# Boost-to-12V.net
KiCad netlist of a schematic drawn in Altium Designer
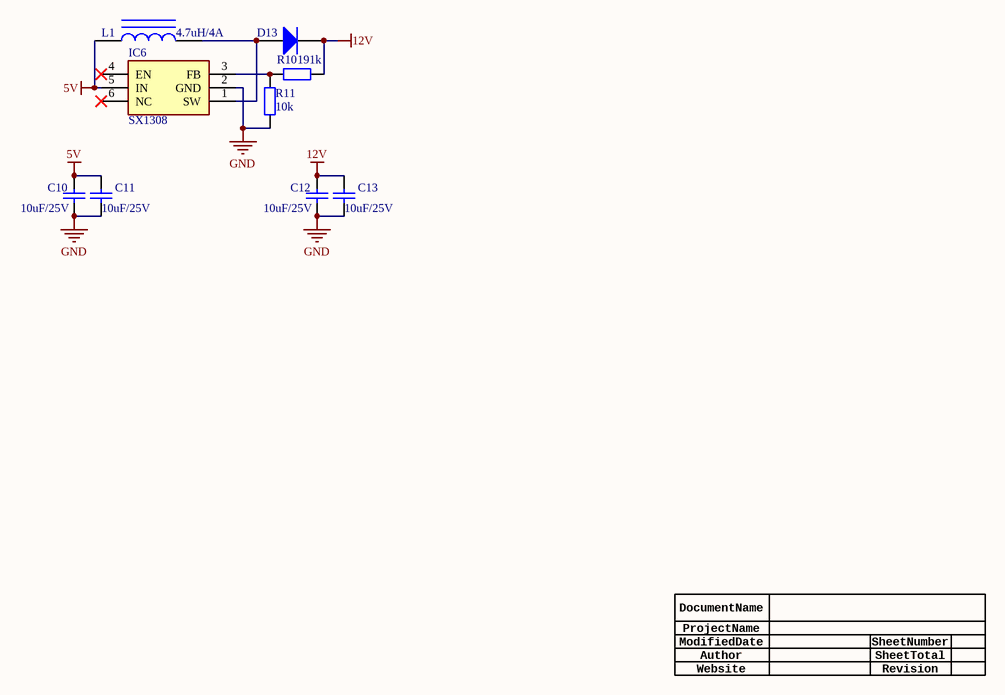
[diagram p0: Boost-to-12V.SchDoc]

(export (version "E")
  (design (tool "Eeschema 10.0.6"))
  (components
    (comp (ref "C10")
      (value "10uF/25V")
      (footprint "CAP-0603")
      (description "X7R")
      (libsource (lib "Power_Lib_Altium") (part "CAP"))
    )
    (comp (ref "C11")
      (value "10uF/25V")
      (footprint "CAP-0603")
      (description "X7R")
      (libsource (lib "Power_Lib_Altium") (part "CAP"))
    )
    (comp (ref "C12")
      (value "10uF/25V")
      (footprint "CAP-0603")
      (description "X7R")
      (libsource (lib "Power_Lib_Altium") (part "CAP"))
    )
    (comp (ref "C13")
      (value "10uF/25V")
      (footprint "CAP-0603")
      (description "X7R")
      (libsource (lib "Power_Lib_Altium") (part "CAP"))
    )
    (comp (ref "D13")
      (value "SS34")
      (footprint "DO-214AC/SMA")
      (description "二极管")
      (libsource (lib "Power_Lib_Altium") (part "DIODE"))
    )
    (comp (ref "IC6")
      (value "SX1308")
      (footprint "SOT-23-6")
      (description "集成升压芯片")
      (libsource (lib "Power_Lib_Altium") (part "SX1308"))
    )
    (comp (ref "L1")
      (value "4.7uH/4A")
      (footprint "SMD_7.3x7.3x4.2mm")
      (description "电感")
      (libsource (lib "Power_Lib_Altium") (part "INDUCTOR"))
    )
    (comp (ref "R10")
      (value "191k")
      (footprint "R-0603")
      (description "贴片电阻")
      (libsource (lib "Power_Lib_Altium") (part "RES"))
    )
    (comp (ref "R11")
      (value "10k")
      (footprint "R-0603")
      (description "贴片电阻")
      (libsource (lib "") (part "RES_1"))
    )
  )
  (nets
    (net (code "1") (name "5V") (class "Default")
      (node (ref "C10") (pin "2") (pinfunction "2_2") (pintype "passive"))
      (node (ref "C11") (pin "2") (pinfunction "2_2") (pintype "passive"))
      (node (ref "IC6") (pin "5") (pinfunction "IN_5") (pintype "passive"))
      (node (ref "L1") (pin "1") (pinfunction "1_1") (pintype "passive"))
    )
    (net (code "2") (name "12V") (class "Default")
      (node (ref "C12") (pin "2") (pinfunction "2_2") (pintype "passive"))
      (node (ref "C13") (pin "2") (pinfunction "2_2") (pintype "passive"))
      (node (ref "D13") (pin "2") (pinfunction "K_2") (pintype "passive"))
      (node (ref "R10") (pin "2") (pinfunction "2_2") (pintype "passive"))
    )
    (net (code "3") (name "GND") (class "Default")
      (node (ref "C10") (pin "1") (pinfunction "1_1") (pintype "passive"))
      (node (ref "C11") (pin "1") (pinfunction "1_1") (pintype "passive"))
      (node (ref "C12") (pin "1") (pinfunction "1_1") (pintype "passive"))
      (node (ref "C13") (pin "1") (pinfunction "1_1") (pintype "passive"))
      (node (ref "IC6") (pin "2") (pinfunction "GND_2") (pintype "passive"))
      (node (ref "R11") (pin "1") (pinfunction "1_1") (pintype "passive"))
    )
    (net (code "4") (name "Net-(D13-A)") (class "Default")
      (node (ref "D13") (pin "1") (pinfunction "A_1") (pintype "passive"))
      (node (ref "IC6") (pin "1") (pinfunction "SW_1") (pintype "passive"))
      (node (ref "L1") (pin "2") (pinfunction "2_2") (pintype "passive"))
    )
    (net (code "5") (name "Net-(IC6-FB)") (class "Default")
      (node (ref "IC6") (pin "3") (pinfunction "FB_3") (pintype "passive"))
      (node (ref "R10") (pin "1") (pinfunction "1_1") (pintype "passive"))
      (node (ref "R11") (pin "2") (pinfunction "2_2") (pintype "passive"))
    )
    (net (code "6") (name "unconnected-(IC6-EN-Pad4)") (class "Default")
      (node (ref "IC6") (pin "4") (pinfunction "EN_4") (pintype "passive+no_connect"))
    )
    (net (code "7") (name "unconnected-(IC6-NC-Pad6)") (class "Default")
      (node (ref "IC6") (pin "6") (pinfunction "NC_6") (pintype "passive+no_connect"))
    )
  )
)
